# ProPrj_transboard.net
KiCad netlist of a schematic drawn in EasyEDA Pro
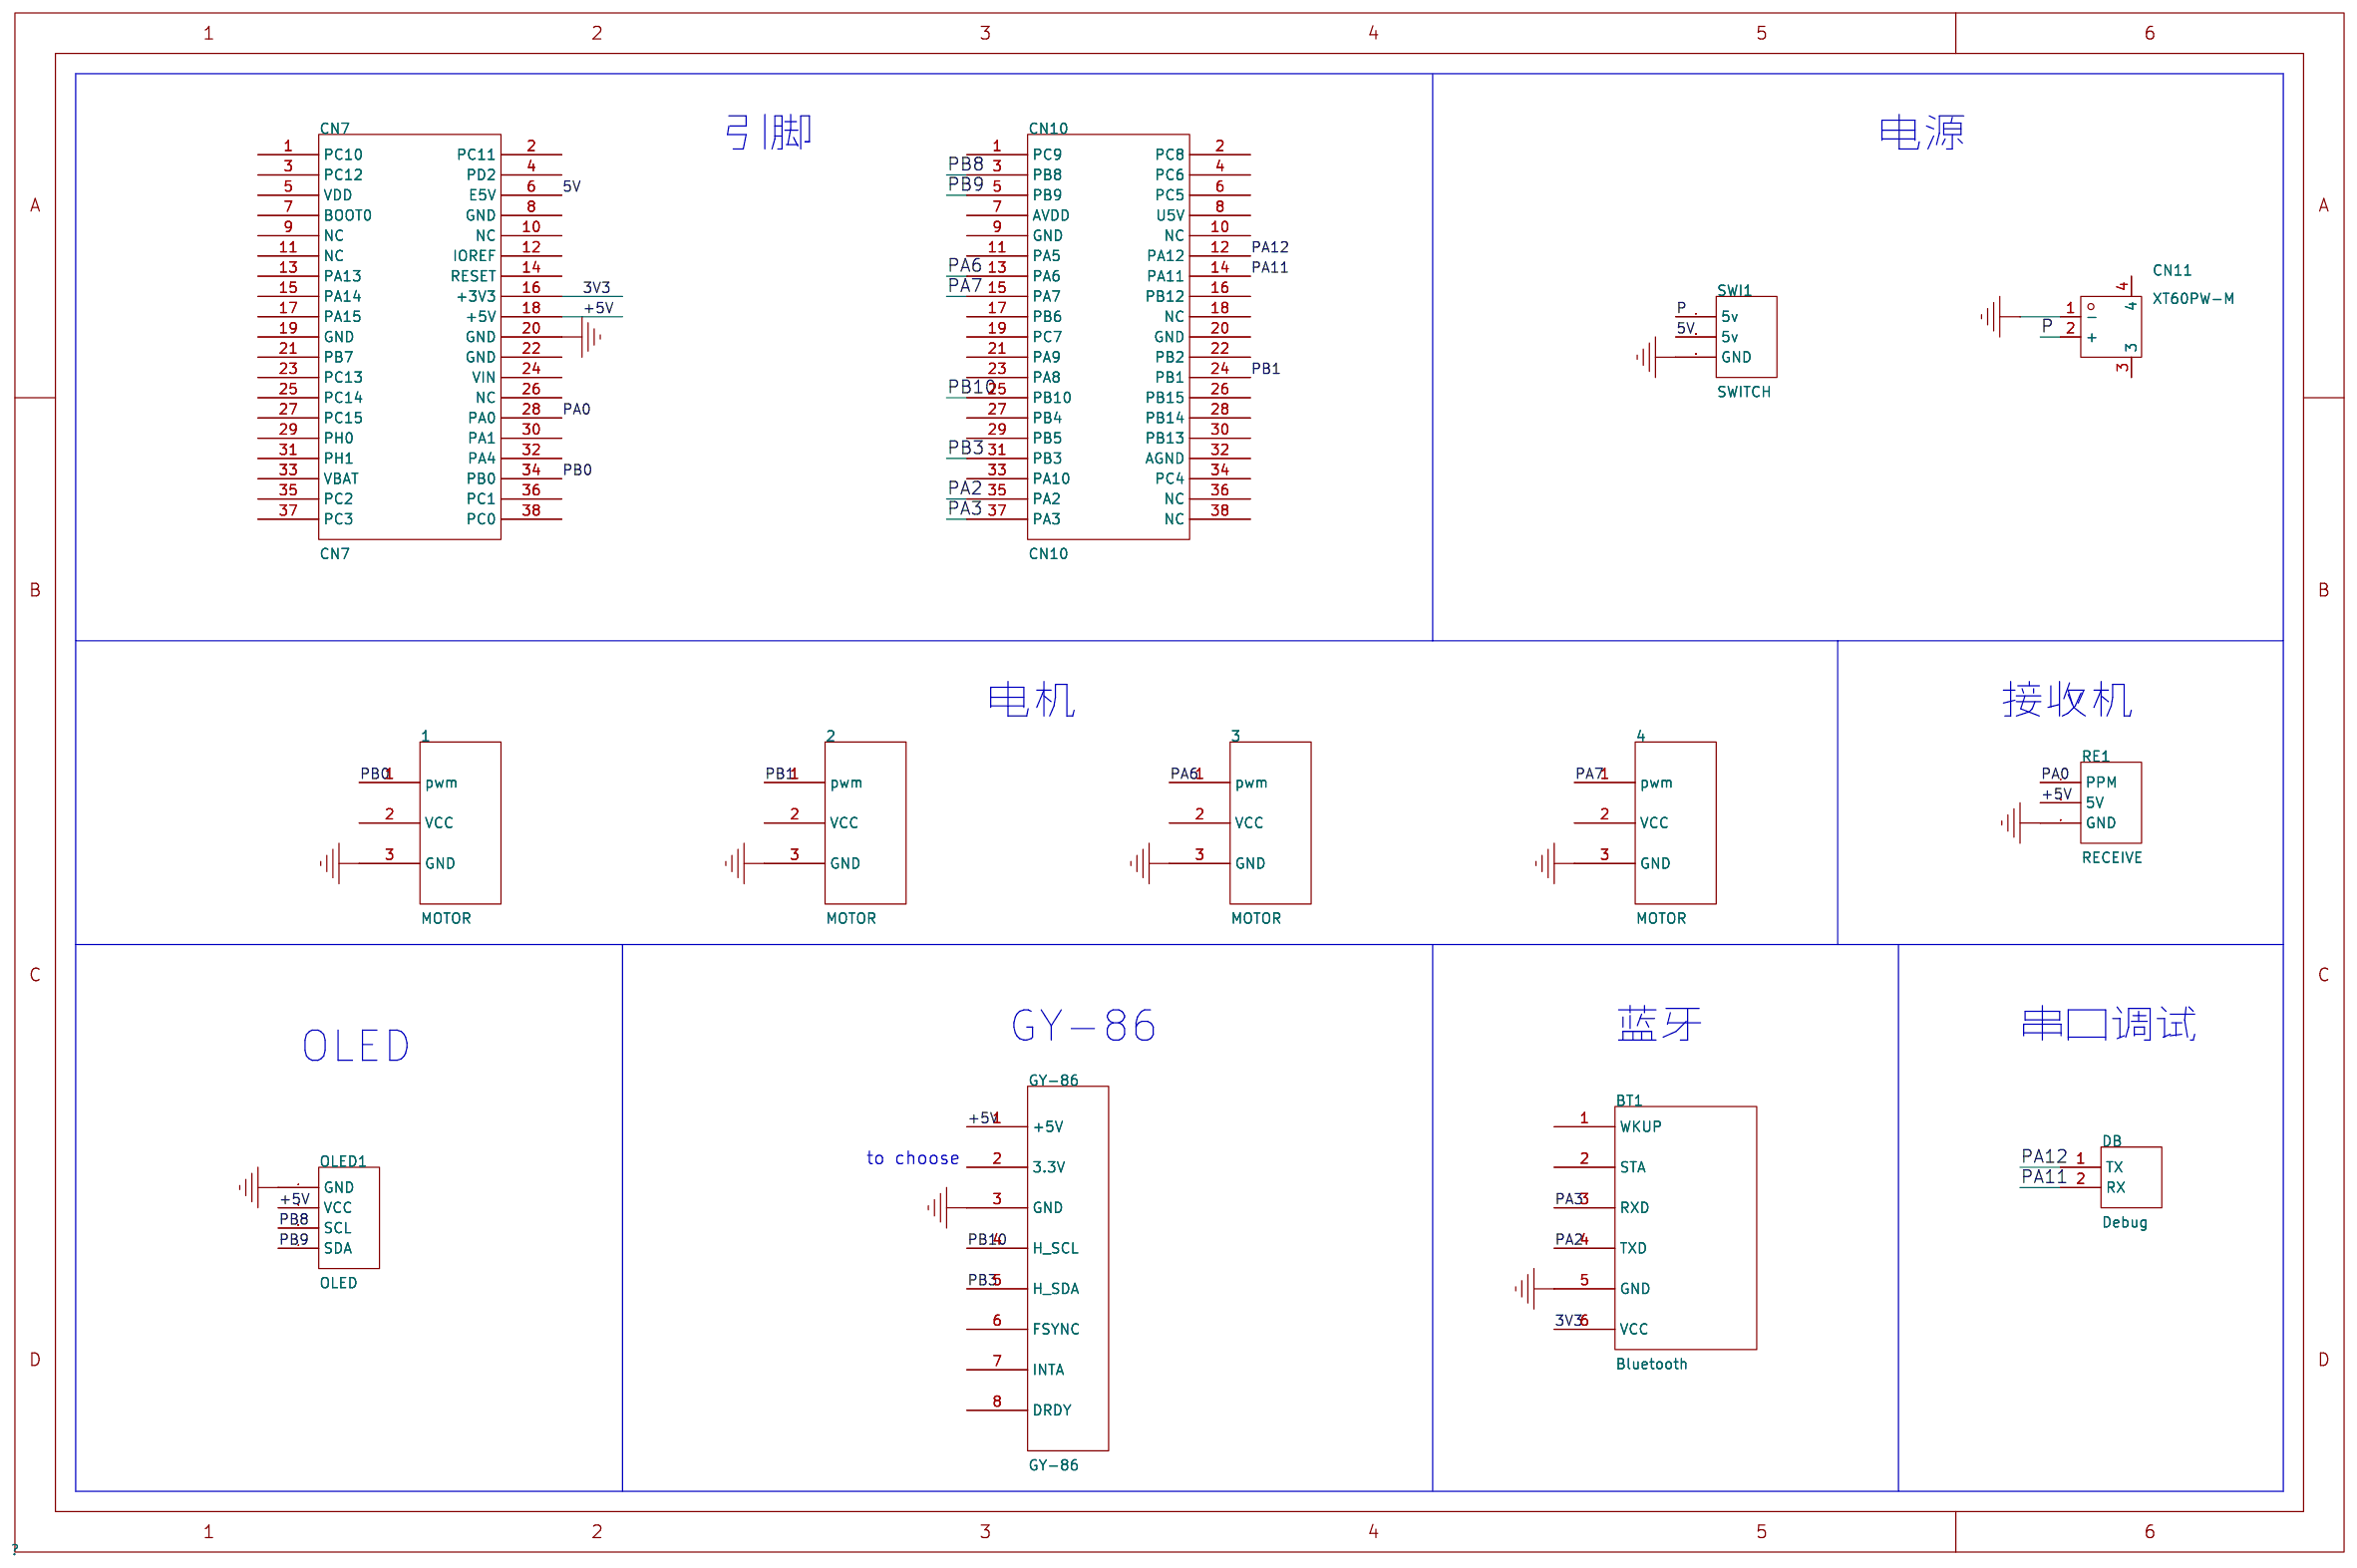
[diagram p0: schematic sheet]

(export (version "E")
  (design (tool "Eeschema 10.0.6"))
  (components
    (comp (ref "1") (value "MOTOR") (libsource (lib "easyedapro") (part "M")))
    (comp (ref "2") (value "MOTOR") (libsource (lib "easyedapro") (part "M")))
    (comp (ref "3") (value "MOTOR") (libsource (lib "easyedapro") (part "M")))
    (comp (ref "4") (value "MOTOR") (libsource (lib "easyedapro") (part "M")))
    (comp (ref "BT1") (value "Bluetooth") (libsource (lib "easyedapro") (part "Bluetooth")))
    (comp (ref "CN7") (value "CN7") (libsource (lib "easyedapro") (part "CN7")))
    (comp (ref "CN10") (value "CN10") (libsource (lib "easyedapro") (part "CN10")))
    (comp (ref "CN11")
      (value "XT60PW-M")
      (footprint "easyedapro:CONN-TH_XT60PW-M")
      (description "类别:-;类型1:-;")
      (fields (field (name "Manufacturer") "AMASS(艾迈斯)"))
      (libsource (lib "easyedapro") (part "XT60PW-M"))
    )
    (comp (ref "DB")
      (value "Debug")
      (description "Header, 2-Pin")
      (libsource (lib "easyedapro") (part "Header 2"))
    )
    (comp (ref "GY-86") (value "GY-86") (libsource (lib "easyedapro") (part "GY-86")))
    (comp (ref "OLED1")
      (value "OLED")
      (description "Header, 4-Pin")
      (libsource (lib "easyedapro") (part "Header 4"))
    )
    (comp (ref "RE1")
      (value "RECEIVE")
      (description "Header, 3-Pin")
      (libsource (lib "easyedapro") (part "Header 3"))
    )
    (comp (ref "SWI1")
      (value "SWITCH")
      (description "Header, 3-Pin")
      (libsource (lib "easyedapro") (part "Header 3_1"))
    )
  )
  (nets
    (net (code "1") (name "/+5V") (class "Default")
      (node (ref "CN7") (pin "18") (pinfunction "+5V_18") (pintype "unspecified"))
      (node (ref "GY-86") (pin "1") (pinfunction "+5V_1") (pintype "unspecified"))
      (node (ref "OLED1") (pin "2") (pinfunction "VCC_2") (pintype "unspecified"))
      (node (ref "RE1") (pin "2") (pinfunction "5V_2") (pintype "unspecified"))
    )
    (net (code "2") (name "/3V3") (class "Default")
      (node (ref "BT1") (pin "6") (pinfunction "VCC_6") (pintype "unspecified"))
      (node (ref "CN7") (pin "16") (pinfunction "+3V3_16") (pintype "unspecified"))
    )
    (net (code "3") (name "/5V") (class "Default")
      (node (ref "CN7") (pin "6") (pinfunction "E5V_6") (pintype "unspecified"))
      (node (ref "SWI1") (pin "2") (pinfunction "5v_2") (pintype "unspecified"))
    )
    (net (code "4") (name "/P") (class "Default")
      (node (ref "CN11") (pin "2") (pinfunction "+_2") (pintype "unspecified"))
      (node (ref "SWI1") (pin "1") (pinfunction "5v_1") (pintype "unspecified"))
    )
    (net (code "5") (name "/PA0") (class "Default")
      (node (ref "CN7") (pin "28") (pinfunction "PA0_28") (pintype "unspecified"))
      (node (ref "RE1") (pin "1") (pinfunction "PPM_1") (pintype "unspecified"))
    )
    (net (code "6") (name "/PA2") (class "Default")
      (node (ref "BT1") (pin "4") (pinfunction "TXD_4") (pintype "unspecified"))
      (node (ref "CN10") (pin "35") (pinfunction "PA2_35") (pintype "unspecified"))
    )
    (net (code "7") (name "/PA3") (class "Default")
      (node (ref "BT1") (pin "3") (pinfunction "RXD_3") (pintype "unspecified"))
      (node (ref "CN10") (pin "37") (pinfunction "PA3_37") (pintype "unspecified"))
    )
    (net (code "8") (name "/PA6") (class "Default")
      (node (ref "3") (pin "1") (pinfunction "pwm_1") (pintype "unspecified"))
      (node (ref "CN10") (pin "13") (pinfunction "PA6_13") (pintype "unspecified"))
    )
    (net (code "9") (name "/PA7") (class "Default")
      (node (ref "4") (pin "1") (pinfunction "pwm_1") (pintype "unspecified"))
      (node (ref "CN10") (pin "15") (pinfunction "PA7_15") (pintype "unspecified"))
    )
    (net (code "10") (name "/PA11") (class "Default")
      (node (ref "CN10") (pin "14") (pinfunction "PA11_14") (pintype "unspecified"))
      (node (ref "DB") (pin "2") (pinfunction "RX_2") (pintype "unspecified"))
    )
    (net (code "11") (name "/PA12") (class "Default")
      (node (ref "CN10") (pin "12") (pinfunction "PA12_12") (pintype "unspecified"))
      (node (ref "DB") (pin "1") (pinfunction "TX_1") (pintype "unspecified"))
    )
    (net (code "12") (name "/PB0") (class "Default")
      (node (ref "1") (pin "1") (pinfunction "pwm_1") (pintype "unspecified"))
      (node (ref "CN7") (pin "34") (pinfunction "PB0_34") (pintype "unspecified"))
    )
    (net (code "13") (name "/PB1") (class "Default")
      (node (ref "2") (pin "1") (pinfunction "pwm_1") (pintype "unspecified"))
      (node (ref "CN10") (pin "24") (pinfunction "PB1_24") (pintype "unspecified"))
    )
    (net (code "14") (name "/PB3") (class "Default")
      (node (ref "CN10") (pin "31") (pinfunction "PB3_31") (pintype "unspecified"))
      (node (ref "GY-86") (pin "5") (pinfunction "H_SDA_5") (pintype "unspecified"))
    )
    (net (code "15") (name "/PB8") (class "Default")
      (node (ref "CN10") (pin "3") (pinfunction "PB8_3") (pintype "unspecified"))
      (node (ref "OLED1") (pin "3") (pinfunction "SCL_3") (pintype "unspecified"))
    )
    (net (code "16") (name "/PB9") (class "Default")
      (node (ref "CN10") (pin "5") (pinfunction "PB9_5") (pintype "unspecified"))
      (node (ref "OLED1") (pin "4") (pinfunction "SDA_4") (pintype "unspecified"))
    )
    (net (code "17") (name "/PB10") (class "Default")
      (node (ref "CN10") (pin "25") (pinfunction "PB10_25") (pintype "unspecified"))
      (node (ref "GY-86") (pin "4") (pinfunction "H_SCL_4") (pintype "unspecified"))
    )
    (net (code "18") (name "GND") (class "Default")
      (node (ref "1") (pin "3") (pinfunction "GND_3") (pintype "unspecified"))
      (node (ref "2") (pin "3") (pinfunction "GND_3") (pintype "unspecified"))
      (node (ref "3") (pin "3") (pinfunction "GND_3") (pintype "unspecified"))
      (node (ref "4") (pin "3") (pinfunction "GND_3") (pintype "unspecified"))
      (node (ref "BT1") (pin "5") (pinfunction "GND_5") (pintype "unspecified"))
      (node (ref "CN11") (pin "1") (pinfunction "-_1") (pintype "unspecified"))
      (node (ref "CN7") (pin "20") (pinfunction "GND_20") (pintype "unspecified"))
      (node (ref "GY-86") (pin "3") (pinfunction "GND_3") (pintype "unspecified"))
      (node (ref "OLED1") (pin "1") (pinfunction "GND_1") (pintype "unspecified"))
      (node (ref "RE1") (pin "3") (pinfunction "GND_3") (pintype "unspecified"))
      (node (ref "SWI1") (pin "3") (pinfunction "GND_3") (pintype "unspecified"))
    )
    (net (code "19") (name "unconnected-(1-VCC-Pad2)") (class "Default")
      (node (ref "1") (pin "2") (pinfunction "VCC_2") (pintype "unspecified"))
    )
    (net (code "20") (name "unconnected-(2-VCC-Pad2)") (class "Default")
      (node (ref "2") (pin "2") (pinfunction "VCC_2") (pintype "unspecified"))
    )
    (net (code "21") (name "unconnected-(3-VCC-Pad2)") (class "Default")
      (node (ref "3") (pin "2") (pinfunction "VCC_2") (pintype "unspecified"))
    )
    (net (code "22") (name "unconnected-(4-VCC-Pad2)") (class "Default")
      (node (ref "4") (pin "2") (pinfunction "VCC_2") (pintype "unspecified"))
    )
    (net (code "23") (name "unconnected-(BT1-STA-Pad2)") (class "Default")
      (node (ref "BT1") (pin "2") (pinfunction "STA_2") (pintype "unspecified"))
    )
    (net (code "24") (name "unconnected-(BT1-WKUP-Pad1)") (class "Default")
      (node (ref "BT1") (pin "1") (pinfunction "WKUP_1") (pintype "unspecified"))
    )
    (net (code "25") (name "unconnected-(CN7-BOOT0-Pad7)") (class "Default")
      (node (ref "CN7") (pin "7") (pinfunction "BOOT0_7") (pintype "unspecified"))
    )
    (net (code "26") (name "unconnected-(CN7-GND-Pad8)") (class "Default")
      (node (ref "CN7") (pin "8") (pinfunction "GND_8") (pintype "unspecified"))
    )
    (net (code "27") (name "unconnected-(CN7-GND-Pad19)") (class "Default")
      (node (ref "CN7") (pin "19") (pinfunction "GND_19") (pintype "unspecified"))
    )
    (net (code "28") (name "unconnected-(CN7-GND-Pad22)") (class "Default")
      (node (ref "CN7") (pin "22") (pinfunction "GND_22") (pintype "unspecified"))
    )
    (net (code "29") (name "unconnected-(CN7-IOREF-Pad12)") (class "Default")
      (node (ref "CN7") (pin "12") (pinfunction "IOREF_12") (pintype "unspecified"))
    )
    (net (code "30") (name "unconnected-(CN7-NC-Pad9)") (class "Default")
      (node (ref "CN7") (pin "9") (pinfunction "NC_9") (pintype "unspecified"))
    )
    (net (code "31") (name "unconnected-(CN7-NC-Pad10)") (class "Default")
      (node (ref "CN7") (pin "10") (pinfunction "NC_10") (pintype "unspecified"))
    )
    (net (code "32") (name "unconnected-(CN7-NC-Pad11)") (class "Default")
      (node (ref "CN7") (pin "11") (pinfunction "NC_11") (pintype "unspecified"))
    )
    (net (code "33") (name "unconnected-(CN7-NC-Pad26)") (class "Default")
      (node (ref "CN7") (pin "26") (pinfunction "NC_26") (pintype "unspecified"))
    )
    (net (code "34") (name "unconnected-(CN7-PA1-Pad30)") (class "Default")
      (node (ref "CN7") (pin "30") (pinfunction "PA1_30") (pintype "unspecified"))
    )
    (net (code "35") (name "unconnected-(CN7-PA4-Pad32)") (class "Default")
      (node (ref "CN7") (pin "32") (pinfunction "PA4_32") (pintype "unspecified"))
    )
    (net (code "36") (name "unconnected-(CN7-PA13-Pad13)") (class "Default")
      (node (ref "CN7") (pin "13") (pinfunction "PA13_13") (pintype "unspecified"))
    )
    (net (code "37") (name "unconnected-(CN7-PA14-Pad15)") (class "Default")
      (node (ref "CN7") (pin "15") (pinfunction "PA14_15") (pintype "unspecified"))
    )
    (net (code "38") (name "unconnected-(CN7-PA15-Pad17)") (class "Default")
      (node (ref "CN7") (pin "17") (pinfunction "PA15_17") (pintype "unspecified"))
    )
    (net (code "39") (name "unconnected-(CN7-PB7-Pad21)") (class "Default")
      (node (ref "CN7") (pin "21") (pinfunction "PB7_21") (pintype "unspecified"))
    )
    (net (code "40") (name "unconnected-(CN7-PC0-Pad38)") (class "Default")
      (node (ref "CN7") (pin "38") (pinfunction "PC0_38") (pintype "unspecified"))
    )
    (net (code "41") (name "unconnected-(CN7-PC1-Pad36)") (class "Default")
      (node (ref "CN7") (pin "36") (pinfunction "PC1_36") (pintype "unspecified"))
    )
    (net (code "42") (name "unconnected-(CN7-PC2-Pad35)") (class "Default")
      (node (ref "CN7") (pin "35") (pinfunction "PC2_35") (pintype "unspecified"))
    )
    (net (code "43") (name "unconnected-(CN7-PC3-Pad37)") (class "Default")
      (node (ref "CN7") (pin "37") (pinfunction "PC3_37") (pintype "unspecified"))
    )
    (net (code "44") (name "unconnected-(CN7-PC10-Pad1)") (class "Default")
      (node (ref "CN7") (pin "1") (pinfunction "PC10_1") (pintype "unspecified"))
    )
    (net (code "45") (name "unconnected-(CN7-PC11-Pad2)") (class "Default")
      (node (ref "CN7") (pin "2") (pinfunction "PC11_2") (pintype "unspecified"))
    )
    (net (code "46") (name "unconnected-(CN7-PC12-Pad3)") (class "Default")
      (node (ref "CN7") (pin "3") (pinfunction "PC12_3") (pintype "unspecified"))
    )
    (net (code "47") (name "unconnected-(CN7-PC13-Pad23)") (class "Default")
      (node (ref "CN7") (pin "23") (pinfunction "PC13_23") (pintype "unspecified"))
    )
    (net (code "48") (name "unconnected-(CN7-PC14-Pad25)") (class "Default")
      (node (ref "CN7") (pin "25") (pinfunction "PC14_25") (pintype "unspecified"))
    )
    (net (code "49") (name "unconnected-(CN7-PC15-Pad27)") (class "Default")
      (node (ref "CN7") (pin "27") (pinfunction "PC15_27") (pintype "unspecified"))
    )
    (net (code "50") (name "unconnected-(CN7-PD2-Pad4)") (class "Default")
      (node (ref "CN7") (pin "4") (pinfunction "PD2_4") (pintype "unspecified"))
    )
    (net (code "51") (name "unconnected-(CN7-PH0-Pad29)") (class "Default")
      (node (ref "CN7") (pin "29") (pinfunction "PH0_29") (pintype "unspecified"))
    )
    (net (code "52") (name "unconnected-(CN7-PH1-Pad31)") (class "Default")
      (node (ref "CN7") (pin "31") (pinfunction "PH1_31") (pintype "unspecified"))
    )
    (net (code "53") (name "unconnected-(CN7-RESET-Pad14)") (class "Default")
      (node (ref "CN7") (pin "14") (pinfunction "RESET_14") (pintype "unspecified"))
    )
    (net (code "54") (name "unconnected-(CN7-VBAT-Pad33)") (class "Default")
      (node (ref "CN7") (pin "33") (pinfunction "VBAT_33") (pintype "unspecified"))
    )
    (net (code "55") (name "unconnected-(CN7-VDD-Pad5)") (class "Default")
      (node (ref "CN7") (pin "5") (pinfunction "VDD_5") (pintype "unspecified"))
    )
    (net (code "56") (name "unconnected-(CN7-VIN-Pad24)") (class "Default")
      (node (ref "CN7") (pin "24") (pinfunction "VIN_24") (pintype "unspecified"))
    )
    (net (code "57") (name "unconnected-(CN10-AGND-Pad32)") (class "Default")
      (node (ref "CN10") (pin "32") (pinfunction "AGND_32") (pintype "unspecified"))
    )
    (net (code "58") (name "unconnected-(CN10-AVDD-Pad7)") (class "Default")
      (node (ref "CN10") (pin "7") (pinfunction "AVDD_7") (pintype "unspecified"))
    )
    (net (code "59") (name "unconnected-(CN10-GND-Pad9)") (class "Default")
      (node (ref "CN10") (pin "9") (pinfunction "GND_9") (pintype "unspecified"))
    )
    (net (code "60") (name "unconnected-(CN10-GND-Pad20)") (class "Default")
      (node (ref "CN10") (pin "20") (pinfunction "GND_20") (pintype "unspecified"))
    )
    (net (code "61") (name "unconnected-(CN10-NC-Pad10)") (class "Default")
      (node (ref "CN10") (pin "10") (pinfunction "NC_10") (pintype "unspecified"))
    )
    (net (code "62") (name "unconnected-(CN10-NC-Pad18)") (class "Default")
      (node (ref "CN10") (pin "18") (pinfunction "NC_18") (pintype "unspecified"))
    )
    (net (code "63") (name "unconnected-(CN10-NC-Pad36)") (class "Default")
      (node (ref "CN10") (pin "36") (pinfunction "NC_36") (pintype "unspecified"))
    )
    (net (code "64") (name "unconnected-(CN10-NC-Pad38)") (class "Default")
      (node (ref "CN10") (pin "38") (pinfunction "NC_38") (pintype "unspecified"))
    )
    (net (code "65") (name "unconnected-(CN10-PA5-Pad11)") (class "Default")
      (node (ref "CN10") (pin "11") (pinfunction "PA5_11") (pintype "unspecified"))
    )
    (net (code "66") (name "unconnected-(CN10-PA8-Pad23)") (class "Default")
      (node (ref "CN10") (pin "23") (pinfunction "PA8_23") (pintype "unspecified"))
    )
    (net (code "67") (name "unconnected-(CN10-PA9-Pad21)") (class "Default")
      (node (ref "CN10") (pin "21") (pinfunction "PA9_21") (pintype "unspecified"))
    )
    (net (code "68") (name "unconnected-(CN10-PA10-Pad33)") (class "Default")
      (node (ref "CN10") (pin "33") (pinfunction "PA10_33") (pintype "unspecified"))
    )
    (net (code "69") (name "unconnected-(CN10-PB2-Pad22)") (class "Default")
      (node (ref "CN10") (pin "22") (pinfunction "PB2_22") (pintype "unspecified"))
    )
    (net (code "70") (name "unconnected-(CN10-PB4-Pad27)") (class "Default")
      (node (ref "CN10") (pin "27") (pinfunction "PB4_27") (pintype "unspecified"))
    )
    (net (code "71") (name "unconnected-(CN10-PB5-Pad29)") (class "Default")
      (node (ref "CN10") (pin "29") (pinfunction "PB5_29") (pintype "unspecified"))
    )
    (net (code "72") (name "unconnected-(CN10-PB6-Pad17)") (class "Default")
      (node (ref "CN10") (pin "17") (pinfunction "PB6_17") (pintype "unspecified"))
    )
    (net (code "73") (name "unconnected-(CN10-PB12-Pad16)") (class "Default")
      (node (ref "CN10") (pin "16") (pinfunction "PB12_16") (pintype "unspecified"))
    )
    (net (code "74") (name "unconnected-(CN10-PB13-Pad30)") (class "Default")
      (node (ref "CN10") (pin "30") (pinfunction "PB13_30") (pintype "unspecified"))
    )
    (net (code "75") (name "unconnected-(CN10-PB14-Pad28)") (class "Default")
      (node (ref "CN10") (pin "28") (pinfunction "PB14_28") (pintype "unspecified"))
    )
    (net (code "76") (name "unconnected-(CN10-PB15-Pad26)") (class "Default")
      (node (ref "CN10") (pin "26") (pinfunction "PB15_26") (pintype "unspecified"))
    )
    (net (code "77") (name "unconnected-(CN10-PC4-Pad34)") (class "Default")
      (node (ref "CN10") (pin "34") (pinfunction "PC4_34") (pintype "unspecified"))
    )
    (net (code "78") (name "unconnected-(CN10-PC5-Pad6)") (class "Default")
      (node (ref "CN10") (pin "6") (pinfunction "PC5_6") (pintype "unspecified"))
    )
    (net (code "79") (name "unconnected-(CN10-PC6-Pad4)") (class "Default")
      (node (ref "CN10") (pin "4") (pinfunction "PC6_4") (pintype "unspecified"))
    )
    (net (code "80") (name "unconnected-(CN10-PC7-Pad19)") (class "Default")
      (node (ref "CN10") (pin "19") (pinfunction "PC7_19") (pintype "unspecified"))
    )
    (net (code "81") (name "unconnected-(CN10-PC8-Pad2)") (class "Default")
      (node (ref "CN10") (pin "2") (pinfunction "PC8_2") (pintype "unspecified"))
    )
    (net (code "82") (name "unconnected-(CN10-PC9-Pad1)") (class "Default")
      (node (ref "CN10") (pin "1") (pinfunction "PC9_1") (pintype "unspecified"))
    )
    (net (code "83") (name "unconnected-(CN10-U5V-Pad8)") (class "Default")
      (node (ref "CN10") (pin "8") (pinfunction "U5V_8") (pintype "unspecified"))
    )
    (net (code "84") (name "unconnected-(CN11-Pad3)") (class "Default")
      (node (ref "CN11") (pin "3") (pinfunction "3_3") (pintype "unspecified"))
    )
    (net (code "85") (name "unconnected-(CN11-Pad4)") (class "Default")
      (node (ref "CN11") (pin "4") (pinfunction "4_4") (pintype "unspecified"))
    )
    (net (code "86") (name "unconnected-(GY-86-3.3V-Pad2)") (class "Default")
      (node (ref "GY-86") (pin "2") (pinfunction "3.3V_2") (pintype "unspecified"))
    )
    (net (code "87") (name "unconnected-(GY-86-DRDY-Pad8)") (class "Default")
      (node (ref "GY-86") (pin "8") (pinfunction "DRDY_8") (pintype "unspecified"))
    )
    (net (code "88") (name "unconnected-(GY-86-FSYNC-Pad6)") (class "Default")
      (node (ref "GY-86") (pin "6") (pinfunction "FSYNC_6") (pintype "unspecified"))
    )
    (net (code "89") (name "unconnected-(GY-86-INTA-Pad7)") (class "Default")
      (node (ref "GY-86") (pin "7") (pinfunction "INTA_7") (pintype "unspecified"))
    )
  )
)
